# tinybee_v1.net
KiCad netlist of a schematic drawn in EAGLE
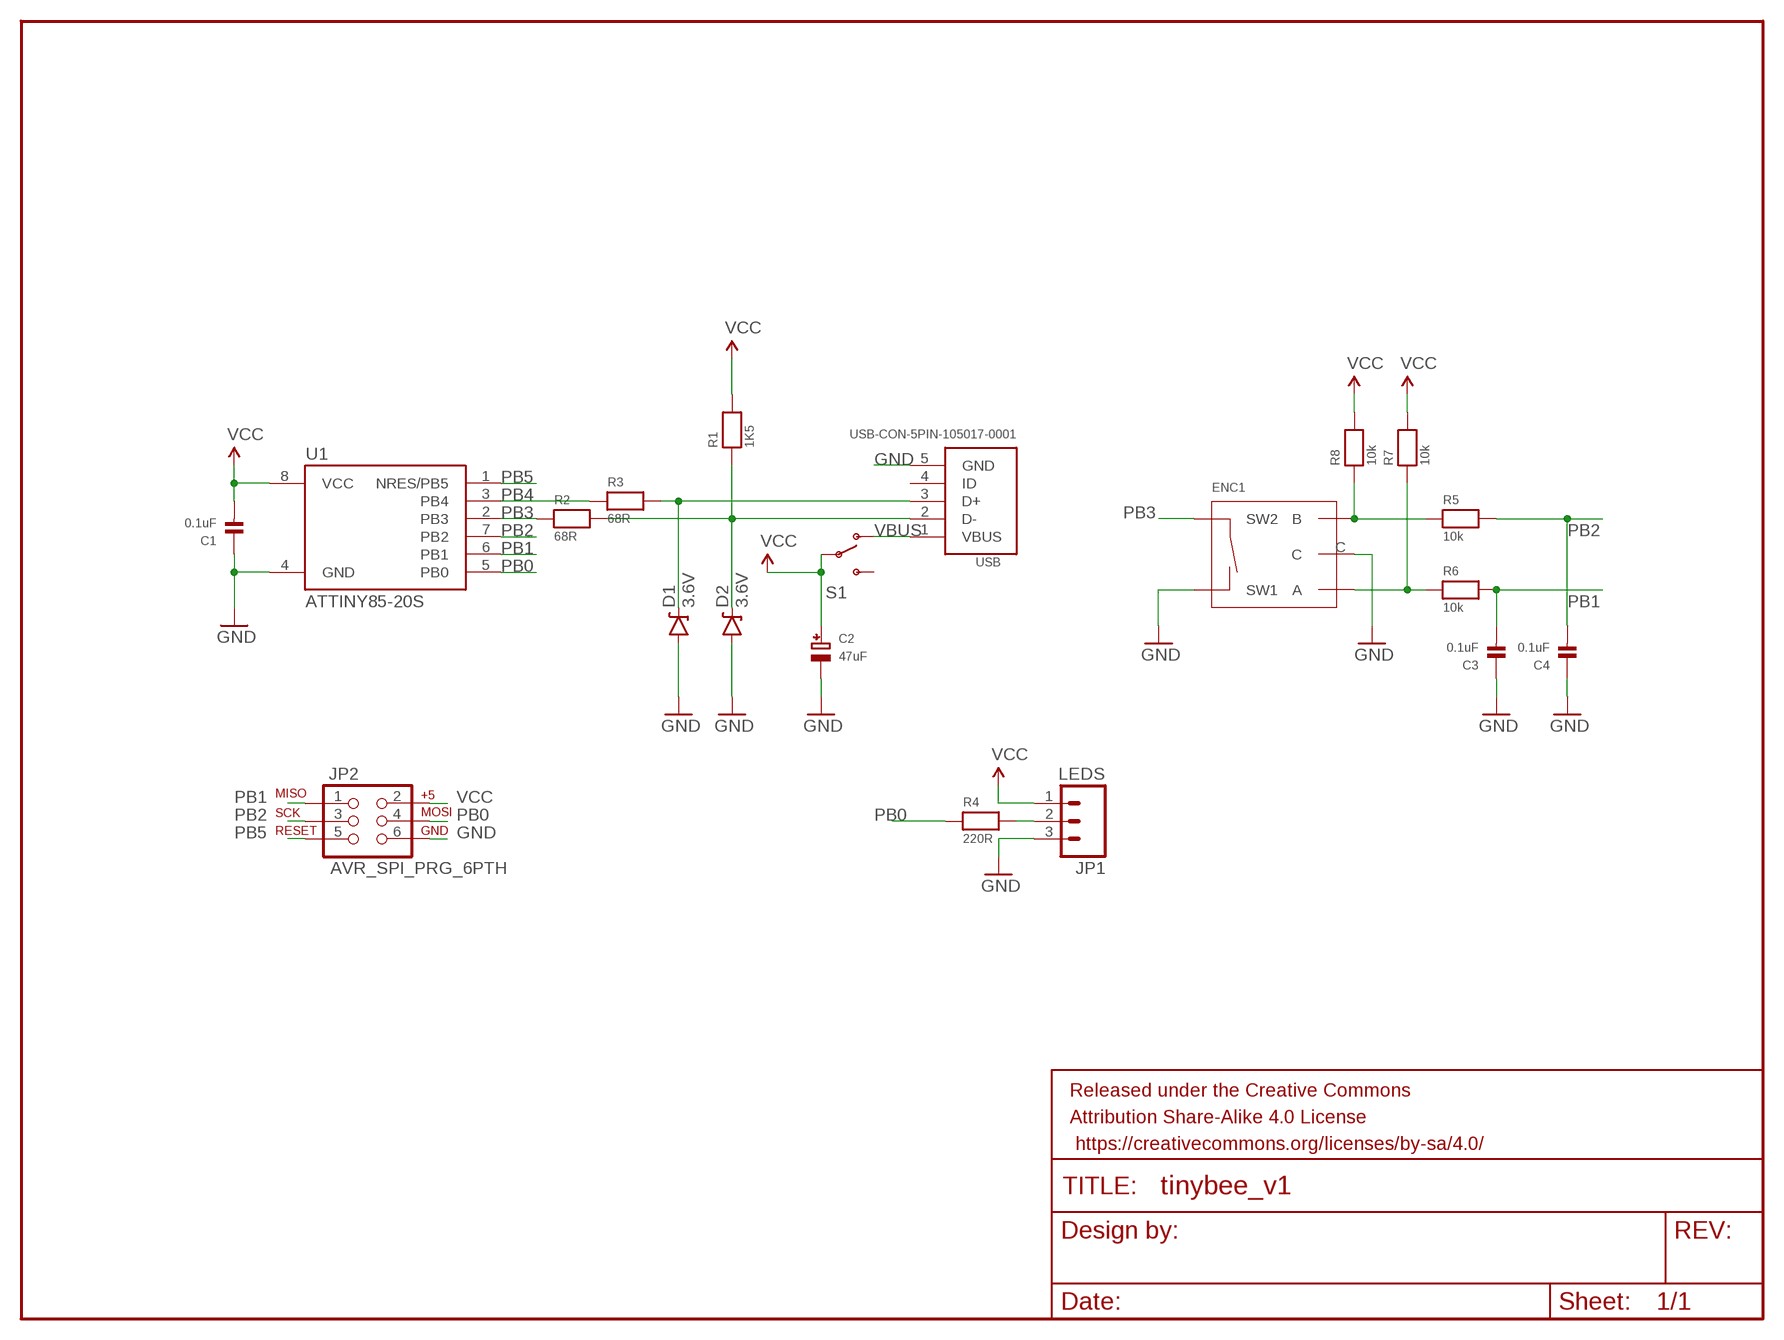
[diagram p0: schematic, sheet 1]

(export (version "E")
  (design (tool "Eeschema 10.0.6"))
  (components
    (comp (ref "C1")
      (value "0.1uF")
      (footprint "eagle-import:0603")
      (libsource (lib "eagle-import") (part "CAP_CERAMIC0603"))
    )
    (comp (ref "C2")
      (value "47uF")
      (footprint "eagle-import:PANASONIC_C")
      (libsource (lib "eagle-import") (part "CAP_ELECTROLYTICPANASONIC_C"))
    )
    (comp (ref "C3")
      (value "0.1uF")
      (footprint "eagle-import:0603")
      (libsource (lib "eagle-import") (part "CAP_CERAMIC0603"))
    )
    (comp (ref "C4")
      (value "0.1uF")
      (footprint "eagle-import:0603")
      (libsource (lib "eagle-import") (part "CAP_CERAMIC0603"))
    )
    (comp (ref "D1")
      (value "3.6V")
      (footprint "eagle-import:SOD-323")
      (libsource (lib "eagle-import") (part "DIODE-ZENER3.3V"))
    )
    (comp (ref "D2")
      (value "3.6V")
      (footprint "eagle-import:SOD-323")
      (libsource (lib "eagle-import") (part "DIODE-ZENER3.3V"))
    )
    (comp (ref "ENC1")
      (value "ROTARY-ENCODER-PEC12R")
      (footprint "eagle-import:ROTARY-ENCODER-PEC12R")
      (libsource (lib "eagle-import") (part "ROTARY-ENCODER-PEC12R"))
    )
    (comp (ref "FRAME1")
      (value "FRAME-LETTER")
      (footprint "eagle-import:CREATIVE_COMMONS")
      (libsource (lib "eagle-import") (part "FRAME-LETTER"))
    )
    (comp (ref "JP1")
      (value "LEDS")
      (footprint "eagle-import:1X03")
      (libsource (lib "eagle-import") (part "M03PTH"))
    )
    (comp (ref "JP2")
      (value "AVR_SPI_PRG_6PTH")
      (footprint "eagle-import:2X3")
      (libsource (lib "eagle-import") (part "AVR_SPI_PRG_6PTH"))
    )
    (comp (ref "R1")
      (value "1K5")
      (footprint "eagle-import:0603")
      (libsource (lib "eagle-import") (part "RESISTOR0603"))
    )
    (comp (ref "R2")
      (value "68R")
      (footprint "eagle-import:0603")
      (libsource (lib "eagle-import") (part "RESISTOR0603"))
    )
    (comp (ref "R3")
      (value "68R")
      (footprint "eagle-import:0603")
      (libsource (lib "eagle-import") (part "RESISTOR0603"))
    )
    (comp (ref "R4")
      (value "220R")
      (footprint "eagle-import:0603")
      (libsource (lib "eagle-import") (part "RESISTOR0603"))
    )
    (comp (ref "R5")
      (value "10k")
      (footprint "eagle-import:0603")
      (libsource (lib "eagle-import") (part "RESISTOR0603"))
    )
    (comp (ref "R6")
      (value "10k")
      (footprint "eagle-import:0603")
      (libsource (lib "eagle-import") (part "RESISTOR0603"))
    )
    (comp (ref "R7")
      (value "10k")
      (footprint "eagle-import:0603")
      (libsource (lib "eagle-import") (part "RESISTOR0603"))
    )
    (comp (ref "R8")
      (value "10k")
      (footprint "eagle-import:0603")
      (libsource (lib "eagle-import") (part "RESISTOR0603"))
    )
    (comp (ref "S1")
      (value "SWITCH-SLIDE-SPDT-RIGHTANGLE-500")
      (footprint "eagle-import:SWITCH-SPDT-RIGHTANGLE-500")
      (libsource (lib "eagle-import") (part "SWITCH-SLIDE-SPDT-RIGHTANGLE-500"))
    )
    (comp (ref "U1")
      (value "ATTINY85-20S")
      (footprint "eagle-import:SOIC8_EIAJ_208MIL")
      (libsource (lib "eagle-import") (part "ATTINY85S-20"))
    )
    (comp (ref "USB")
      (value "USB-CON-5PIN-105017-0001")
      (footprint "eagle-import:USB-MICRO-MOLEX-105017-0001")
      (libsource (lib "eagle-import") (part "USB-CON-5PIN-105017-0001"))
    )
  )
  (nets
    (net (code "1") (name "/PB0") (class "Default")
      (node (ref "JP2") (pin "4") (pinfunction "4_4") (pintype "passive"))
      (node (ref "R4") (pin "1") (pinfunction "1_1") (pintype "passive"))
      (node (ref "U1") (pin "5") (pinfunction "PB0_5") (pintype "bidirectional"))
    )
    (net (code "2") (name "/PB1") (class "Default")
      (node (ref "C3") (pin "2") (pinfunction "P$2_2") (pintype "passive"))
      (node (ref "JP2") (pin "1") (pinfunction "1_1") (pintype "passive"))
      (node (ref "R6") (pin "2") (pinfunction "2_2") (pintype "passive"))
      (node (ref "U1") (pin "6") (pinfunction "PB1_6") (pintype "bidirectional"))
    )
    (net (code "3") (name "/PB2") (class "Default")
      (node (ref "C4") (pin "2") (pinfunction "P$2_2") (pintype "passive"))
      (node (ref "JP2") (pin "3") (pinfunction "3_3") (pintype "passive"))
      (node (ref "R5") (pin "2") (pinfunction "2_2") (pintype "passive"))
      (node (ref "U1") (pin "7") (pinfunction "PB2_7") (pintype "bidirectional"))
    )
    (net (code "4") (name "/PB3") (class "Default")
      (node (ref "ENC1") (pin "SW2") (pinfunction "SW2_SW2") (pintype "bidirectional"))
      (node (ref "R2") (pin "1") (pinfunction "1_1") (pintype "passive"))
      (node (ref "U1") (pin "2") (pinfunction "PB3_2") (pintype "bidirectional"))
    )
    (net (code "5") (name "/PB4") (class "Default")
      (node (ref "R3") (pin "1") (pinfunction "1_1") (pintype "passive"))
      (node (ref "U1") (pin "3") (pinfunction "PB4_3") (pintype "bidirectional"))
    )
    (net (code "6") (name "/PB5") (class "Default")
      (node (ref "JP2") (pin "5") (pinfunction "5_5") (pintype "passive"))
      (node (ref "U1") (pin "1") (pinfunction "NRES/PB5_1") (pintype "bidirectional"))
    )
    (net (code "7") (name "/VBUS") (class "Default")
      (node (ref "S1") (pin "SW1") (pinfunction "1_SW1") (pintype "bidirectional"))
      (node (ref "USB") (pin "1") (pinfunction "VBUS_1") (pintype "power_in"))
    )
    (net (code "8") (name "GND") (class "Default")
      (node (ref "C1") (pin "1") (pinfunction "P$1_1") (pintype "passive"))
      (node (ref "C2") (pin "-") (pinfunction "-_-") (pintype "passive"))
      (node (ref "C3") (pin "1") (pinfunction "P$1_1") (pintype "passive"))
      (node (ref "C4") (pin "1") (pinfunction "P$1_1") (pintype "passive"))
      (node (ref "D1") (pin "A") (pinfunction "A_A") (pintype "passive"))
      (node (ref "D2") (pin "A") (pinfunction "A_A") (pintype "passive"))
      (node (ref "ENC1") (pin "C") (pinfunction "C_C") (pintype "input"))
      (node (ref "ENC1") (pin "SW1") (pinfunction "SW1_SW1") (pintype "bidirectional"))
      (node (ref "JP1") (pin "3") (pinfunction "3_3") (pintype "passive"))
      (node (ref "JP2") (pin "6") (pinfunction "6_6") (pintype "passive"))
      (node (ref "U1") (pin "4") (pinfunction "GND_4") (pintype "power_in"))
      (node (ref "USB") (pin "5") (pinfunction "GND_5") (pintype "power_in"))
    )
    (net (code "9") (name "Net-(ENC1-PadA)") (class "Default")
      (node (ref "ENC1") (pin "A") (pinfunction "A_A") (pintype "output"))
      (node (ref "R6") (pin "1") (pinfunction "1_1") (pintype "passive"))
      (node (ref "R7") (pin "1") (pinfunction "1_1") (pintype "passive"))
    )
    (net (code "10") (name "Net-(ENC1-PadB)") (class "Default")
      (node (ref "ENC1") (pin "B") (pinfunction "B_B") (pintype "output"))
      (node (ref "R5") (pin "1") (pinfunction "1_1") (pintype "passive"))
      (node (ref "R8") (pin "1") (pinfunction "1_1") (pintype "passive"))
    )
    (net (code "11") (name "Net-(JP1-Pad2)") (class "Default")
      (node (ref "JP1") (pin "2") (pinfunction "2_2") (pintype "passive"))
      (node (ref "R4") (pin "2") (pinfunction "2_2") (pintype "passive"))
    )
    (net (code "12") (name "Net-(USB-D+)") (class "Default")
      (node (ref "D1") (pin "C") (pinfunction "C_C") (pintype "passive"))
      (node (ref "R3") (pin "2") (pinfunction "2_2") (pintype "passive"))
      (node (ref "USB") (pin "3") (pinfunction "D+_3") (pintype "bidirectional"))
    )
    (net (code "13") (name "Net-(USB-D-)") (class "Default")
      (node (ref "D2") (pin "C") (pinfunction "C_C") (pintype "passive"))
      (node (ref "R1") (pin "1") (pinfunction "1_1") (pintype "passive"))
      (node (ref "R2") (pin "2") (pinfunction "2_2") (pintype "passive"))
      (node (ref "USB") (pin "2") (pinfunction "D-_2") (pintype "bidirectional"))
    )
    (net (code "14") (name "VCC") (class "Default")
      (node (ref "C1") (pin "2") (pinfunction "P$2_2") (pintype "passive"))
      (node (ref "C2") (pin "+") (pinfunction "+_+") (pintype "passive"))
      (node (ref "JP1") (pin "1") (pinfunction "1_1") (pintype "passive"))
      (node (ref "JP2") (pin "2") (pinfunction "2_2") (pintype "passive"))
      (node (ref "R1") (pin "2") (pinfunction "2_2") (pintype "passive"))
      (node (ref "R7") (pin "2") (pinfunction "2_2") (pintype "passive"))
      (node (ref "R8") (pin "2") (pinfunction "2_2") (pintype "passive"))
      (node (ref "S1") (pin "SWC") (pinfunction "COMMON_SWC") (pintype "bidirectional"))
      (node (ref "U1") (pin "8") (pinfunction "VCC_8") (pintype "power_in"))
    )
    (net (code "15") (name "unconnected-(S1-2-PadSW2)") (class "Default")
      (node (ref "S1") (pin "SW2") (pinfunction "2_SW2") (pintype "bidirectional"))
    )
    (net (code "16") (name "unconnected-(USB-ID-Pad4)") (class "Default")
      (node (ref "USB") (pin "4") (pinfunction "ID_4") (pintype "bidirectional"))
    )
  )
)
